# TPS62745.net
KiCad netlist of a schematic drawn in EAGLE
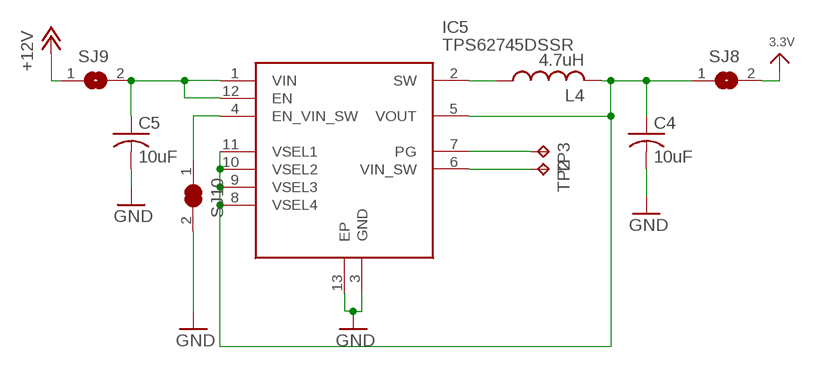
[diagram p0: schematic, sheet 1]

(export (version "E")
  (design (tool "Eeschema 10.0.6"))
  (components
    (comp (ref "C4")
      (value "10uF")
      (footprint "eagle-import:C3216")
      (libsource (lib "eagle-import") (part "C-USC3216"))
    )
    (comp (ref "C5")
      (value "10uF")
      (footprint "eagle-import:C3216")
      (libsource (lib "eagle-import") (part "C-USC3216"))
    )
    (comp (ref "IC5")
      (value "TPS62745DSSR")
      (footprint "eagle-import:SON50P200X300X80-13N")
      (fields (field (name "MOUSER_PART_NUMBER") "595-TPS62745DSSR"))
      (libsource (lib "eagle-import") (part "TPS62745DSSR"))
    )
    (comp (ref "L4")
      (value "4.7uH")
      (footprint "eagle-import:L1210")
      (libsource (lib "eagle-import") (part "L-USL1210"))
    )
    (comp (ref "SJ8") (value "SJ") (footprint "eagle-import:SJ") (libsource (lib "eagle-import") (part "SJ")))
    (comp (ref "SJ9") (value "SJ") (footprint "eagle-import:SJ") (libsource (lib "eagle-import") (part "SJ")))
    (comp (ref "SJ10")
      (value "SOLDERJUMPER_CLOSED")
      (footprint "eagle-import:SOLDERJUMPER_CLOSEDWIRE")
      (libsource (lib "eagle-import") (part "SOLDERJUMPER_CLOSED"))
    )
    (comp (ref "TP2")
      (value "TPTP08R")
      (footprint "eagle-import:TP08R")
      (libsource (lib "eagle-import") (part "TPTP08R"))
    )
    (comp (ref "TP3")
      (value "TPTP08R")
      (footprint "eagle-import:TP08R")
      (libsource (lib "eagle-import") (part "TPTP08R"))
    )
  )
  (nets
    (net (code "1") (name "+12V") (class "Default")
      (node (ref "SJ9") (pin "1") (pinfunction "1_1") (pintype "passive"))
    )
    (net (code "2") (name "3.3V") (class "Default")
      (node (ref "SJ8") (pin "2") (pinfunction "2_2") (pintype "passive"))
    )
    (net (code "3") (name "GND") (class "Default")
      (node (ref "C4") (pin "2") (pinfunction "2_2") (pintype "passive"))
      (node (ref "C5") (pin "2") (pinfunction "2_2") (pintype "passive"))
      (node (ref "IC5") (pin "13") (pinfunction "EP_13") (pintype "bidirectional"))
      (node (ref "IC5") (pin "3") (pinfunction "GND_3") (pintype "bidirectional"))
      (node (ref "SJ10") (pin "2") (pinfunction "2_2") (pintype "passive"))
    )
    (net (code "4") (name "Net-(IC5-EN)") (class "Default")
      (node (ref "C5") (pin "1") (pinfunction "1_1") (pintype "passive"))
      (node (ref "IC5") (pin "1") (pinfunction "VIN_1") (pintype "bidirectional"))
      (node (ref "IC5") (pin "12") (pinfunction "EN_12") (pintype "bidirectional"))
      (node (ref "SJ9") (pin "2") (pinfunction "2_2") (pintype "passive"))
    )
    (net (code "5") (name "Net-(IC5-EN_VIN_SW)") (class "Default")
      (node (ref "IC5") (pin "4") (pinfunction "EN_VIN_SW_4") (pintype "bidirectional"))
      (node (ref "SJ10") (pin "1") (pinfunction "1_1") (pintype "passive"))
    )
    (net (code "6") (name "Net-(IC5-PG)") (class "Default")
      (node (ref "IC5") (pin "7") (pinfunction "PG_7") (pintype "bidirectional"))
      (node (ref "TP3") (pin "TP") (pinfunction "TP_TP") (pintype "input"))
    )
    (net (code "7") (name "Net-(IC5-SW)") (class "Default")
      (node (ref "IC5") (pin "2") (pinfunction "SW_2") (pintype "bidirectional"))
      (node (ref "L4") (pin "1") (pinfunction "1_1") (pintype "passive"))
    )
    (net (code "8") (name "Net-(IC5-VIN_SW)") (class "Default")
      (node (ref "IC5") (pin "6") (pinfunction "VIN_SW_6") (pintype "bidirectional"))
      (node (ref "TP2") (pin "TP") (pinfunction "TP_TP") (pintype "input"))
    )
    (net (code "9") (name "Net-(IC5-VOUT)") (class "Default")
      (node (ref "C4") (pin "1") (pinfunction "1_1") (pintype "passive"))
      (node (ref "IC5") (pin "10") (pinfunction "VSEL2_10") (pintype "bidirectional"))
      (node (ref "IC5") (pin "11") (pinfunction "VSEL1_11") (pintype "bidirectional"))
      (node (ref "IC5") (pin "5") (pinfunction "VOUT_5") (pintype "bidirectional"))
      (node (ref "IC5") (pin "8") (pinfunction "VSEL4_8") (pintype "bidirectional"))
      (node (ref "IC5") (pin "9") (pinfunction "VSEL3_9") (pintype "bidirectional"))
      (node (ref "L4") (pin "2") (pinfunction "2_2") (pintype "passive"))
      (node (ref "SJ8") (pin "1") (pinfunction "1_1") (pintype "passive"))
    )
  )
)
